# Hecquyn_SCH_Proto1_210523.net
KiCad netlist of a schematic drawn in Altium Designer
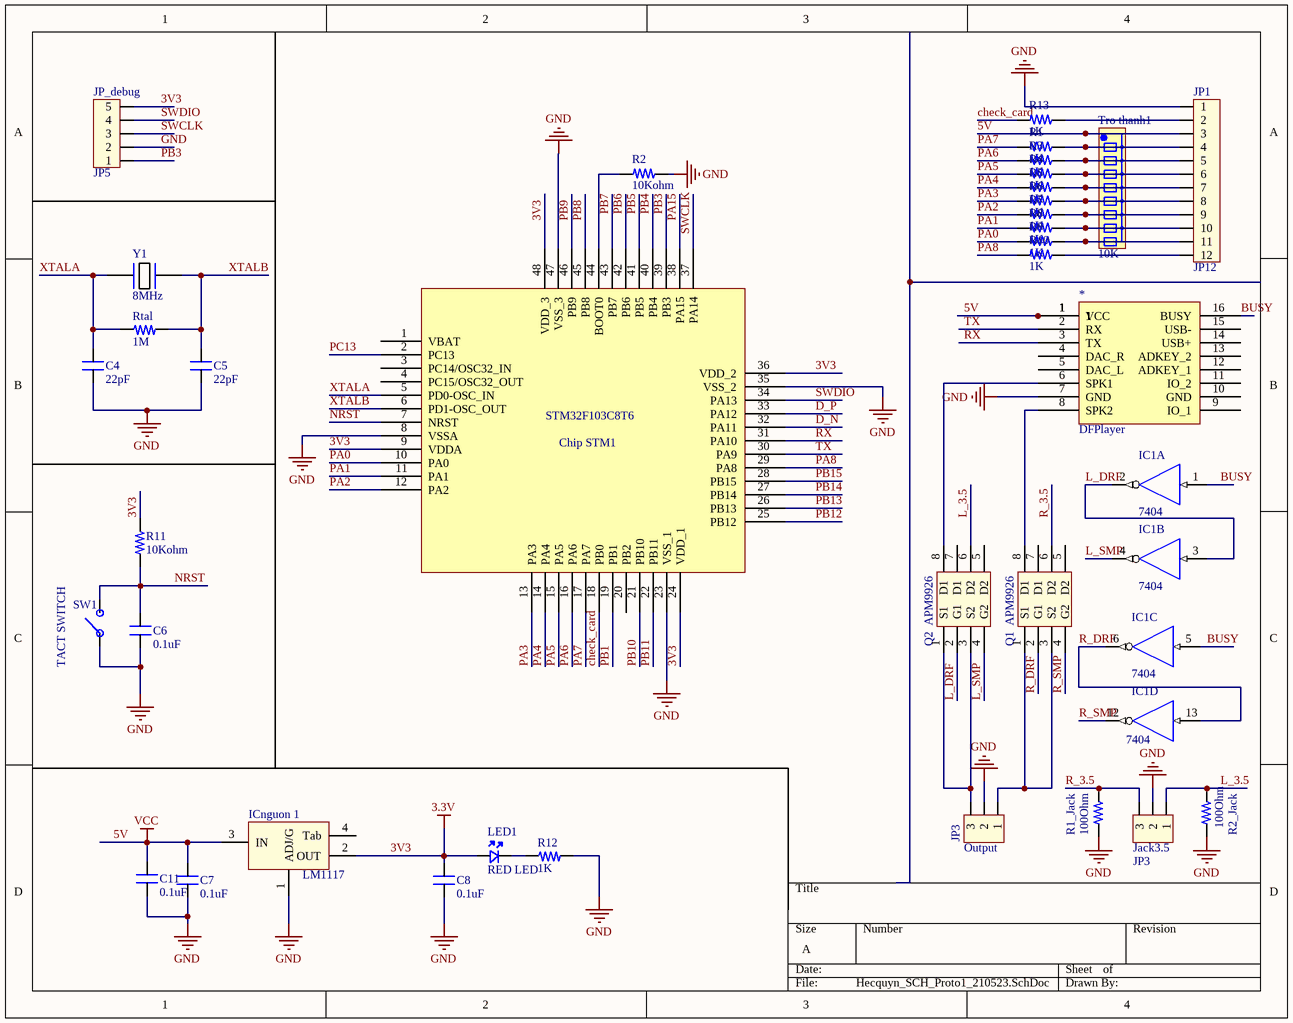
[diagram p0: Hecquyn_SCH_Proto1_210523.SchDoc]

(export (version "E")
  (design (tool "Eeschema 10.0.6"))
  (components
    (comp (ref "*")
      (value "DFPlayer")
      (footprint "DFplayer")
      (libsource (lib "Playersmd") (part "Component_1"))
    )
    (comp (ref "C4")
      (value "22pF")
      (footprint "CAP_0805")
      (description "22pF ±5% 50V Ceramic Capacitor C0G, NP0 0805 (2012 Metric)")
      (fields
        (field (name "MANUFACTURER") "KEMET")
        (field (name "MANUFACTURER PART NUMBER") "C0805C220J5GACTU")
      )
      (libsource (lib "STM_SCH_LIB") (part "CAP_22pF-50V-5%-0805"))
    )
    (comp (ref "C5")
      (value "22pF")
      (footprint "CAP_0805")
      (description "22pF ±5% 50V Ceramic Capacitor C0G, NP0 0805 (2012 Metric)")
      (fields
        (field (name "MANUFACTURER") "KEMET")
        (field (name "MANUFACTURER PART NUMBER") "C0805C220J5GACTU")
      )
      (libsource (lib "STM_SCH_LIB") (part "CAP_22pF-50V-5%-0805"))
    )
    (comp (ref "C6")
      (value "0.1uF")
      (footprint "CAP_0805")
      (description "0.1µF ±5% 50V Ceramic Capacitor X7R 0805 (2012 Metric)")
      (fields
        (field (name "MANUFACTURER") "KEMET")
        (field (name "MANUFACTURING PART NUMBER") "C0805C104J5RACTU")
      )
      (libsource (lib "STM_SCH_LIB") (part "CAP_0.1uF-50V-5%-0805"))
    )
    (comp (ref "C7")
      (value "0.1uF")
      (footprint "CAP_0805")
      (description "0.1µF ±5% 50V Ceramic Capacitor X7R 0805 (2012 Metric)")
      (fields
        (field (name "MANUFACTURER") "KEMET")
        (field (name "MANUFACTURING PART NUMBER") "C0805C104J5RACTU")
      )
      (libsource (lib "STM_SCH_LIB") (part "CAP_0.1uF-50V-5%-0805"))
    )
    (comp (ref "C8")
      (value "0.1uF")
      (footprint "CAP_0805")
      (description "0.1µF ±5% 50V Ceramic Capacitor X7R 0805 (2012 Metric)")
      (fields
        (field (name "MANUFACTURER") "KEMET")
        (field (name "MANUFACTURING PART NUMBER") "C0805C104J5RACTU")
      )
      (libsource (lib "STM_SCH_LIB") (part "CAP_0.1uF-50V-5%-0805"))
    )
    (comp (ref "C11")
      (value "0.1uF")
      (footprint "CAP_0805")
      (description "0.1µF ±5% 50V Ceramic Capacitor X7R 0805 (2012 Metric)")
      (fields
        (field (name "MANUFACTURER") "KEMET")
        (field (name "MANUFACTURING PART NUMBER") "C0805C104J5RACTU")
      )
      (libsource (lib "STM_SCH_LIB") (part "CAP_0.1uF-50V-5%-0805"))
    )
    (comp (ref "Chip STM1")
      (value "STM32F103C8T6")
      (footprint "LQFP-48_19.6_393_58X11_SMD")
      (description "ARM® Cortex®-M3 STM32F1 Microcontroller IC 32-Bit 72MHz 64KB (64K x 8) FLASH")
      (fields (field (name "MANUFACTURER") "STMicroelectronics"))
      (libsource (lib "STM_SCH_LIB") (part "IC-STM32F103C8T6 _1"))
    )
    (comp (ref "IC1")
      (value "7404")
      (footprint "DIP14/W0.3")
      (description "Hex Inverter")
      (libsource (lib "syhaunguyen") (part "7404"))
    )
    (comp (ref "ICnguon 1")
      (value "LM1117")
      (footprint "SOT223-4N")
      (description "3v3")
      (libsource (lib "syhaunguyen") (part "LM1117"))
    )
    (comp (ref "Jack3.5")
      (value "JP3")
      (footprint "CON3")
      (description "Connector 3")
      (libsource (lib "syhaunguyen") (part "Con3"))
    )
    (comp (ref "JP1")
      (value "JP12")
      (footprint "CON12")
      (description "Connector 12")
      (libsource (lib "syhaunguyen") (part "Con12"))
    )
    (comp (ref "JP_debug")
      (value "JP5")
      (footprint "CON5")
      (description "Connector 5")
      (libsource (lib "syhaunguyen") (part "Con5"))
    )
    (comp (ref "LED1")
      (value "RED LED")
      (footprint "LED_0805")
      (description "Red 621nm LED Indication - Discrete 2V 0805 (2012 Metric)")
      (fields
        (field (name "MANUFACTURER") "Lite-On Inc.")
        (field (name "MANUFACTURER PART NUMBER") "LTST-C170EKT")
      )
      (libsource (lib "STM_SCH_LIB") (part "LED-RED_10mA-0805"))
    )
    (comp (ref "Output")
      (value "JP3")
      (footprint "CON3")
      (description "Connector 3")
      (libsource (lib "syhaunguyen") (part "Con3"))
    )
    (comp (ref "Q1")
      (value "APM9926")
      (footprint "SO-8")
      (description "Dual P-Channel Enhancement Mode MOSFET")
      (libsource (lib "syhaunguyen") (part "APM4953"))
    )
    (comp (ref "Q2")
      (value "APM9926")
      (footprint "SO-8")
      (description "Dual P-Channel Enhancement Mode MOSFET")
      (libsource (lib "syhaunguyen") (part "APM4953"))
    )
    (comp (ref "R1")
      (value "1K")
      (footprint "RES_0805")
      (description "1 kOhms ±1% 0.125W, 1/8W Chip Resistor 0805 (2012 Metric) Moisture Resistant Thick Film")
      (fields (field (name "MANUFACTURER") "垈㎵á") (field (name "MANUFACTURER PART NUMBER") "RC0805FR-071KL"))
      (libsource (lib "STM_SCH_LIB") (part "RES_1K-0.125W-1%-0805"))
    )
    (comp (ref "R1_Jack")
      (value "100Ohm")
      (footprint "RES_0805")
      (description "1 kOhms ±1% 0.125W, 1/8W Chip Resistor 0805 (2012 Metric) Moisture Resistant Thick Film")
      (fields (field (name "MANUFACTURER") "垈㎵á") (field (name "MANUFACTURER PART NUMBER") "RC0805FR-071KL"))
      (libsource (lib "STM_SCH_LIB") (part "RES_1K-0.125W-1%-0805"))
    )
    (comp (ref "R2")
      (value "10Kohm")
      (footprint "RES_0805")
      (description "10 kOhms ±1% 0.125W, 1/8W Chip Resistor 0805 (2012 Metric) Moisture Resistant Thick Film")
      (fields
        (field (name "MANUFACTURER") "Yageo")
        (field (name "MANUFACTURING PART NUMBER") "RC0805FR-0710KL")
      )
      (libsource (lib "STM_SCH_LIB") (part "RES_10K-0.125W-1%-0805"))
    )
    (comp (ref "R2_Jack")
      (value "100Ohm")
      (footprint "RES_0805")
      (description "1 kOhms ±1% 0.125W, 1/8W Chip Resistor 0805 (2012 Metric) Moisture Resistant Thick Film")
      (fields (field (name "MANUFACTURER") "垈㎵á") (field (name "MANUFACTURER PART NUMBER") "RC0805FR-071KL"))
      (libsource (lib "STM_SCH_LIB") (part "RES_1K-0.125W-1%-0805"))
    )
    (comp (ref "R3")
      (value "1K")
      (footprint "RES_0805")
      (description "1 kOhms ±1% 0.125W, 1/8W Chip Resistor 0805 (2012 Metric) Moisture Resistant Thick Film")
      (fields (field (name "MANUFACTURER") "垈㎵á") (field (name "MANUFACTURER PART NUMBER") "RC0805FR-071KL"))
      (libsource (lib "STM_SCH_LIB") (part "RES_1K-0.125W-1%-0805"))
    )
    (comp (ref "R4")
      (value "1K")
      (footprint "RES_0805")
      (description "1 kOhms ±1% 0.125W, 1/8W Chip Resistor 0805 (2012 Metric) Moisture Resistant Thick Film")
      (fields (field (name "MANUFACTURER") "垈㎵á") (field (name "MANUFACTURER PART NUMBER") "RC0805FR-071KL"))
      (libsource (lib "STM_SCH_LIB") (part "RES_1K-0.125W-1%-0805"))
    )
    (comp (ref "R5")
      (value "1K")
      (footprint "RES_0805")
      (description "1 kOhms ±1% 0.125W, 1/8W Chip Resistor 0805 (2012 Metric) Moisture Resistant Thick Film")
      (fields (field (name "MANUFACTURER") "垈㎵á") (field (name "MANUFACTURER PART NUMBER") "RC0805FR-071KL"))
      (libsource (lib "STM_SCH_LIB") (part "RES_1K-0.125W-1%-0805"))
    )
    (comp (ref "R6")
      (value "1K")
      (footprint "RES_0805")
      (description "1 kOhms ±1% 0.125W, 1/8W Chip Resistor 0805 (2012 Metric) Moisture Resistant Thick Film")
      (fields (field (name "MANUFACTURER") "垈㎵á") (field (name "MANUFACTURER PART NUMBER") "RC0805FR-071KL"))
      (libsource (lib "STM_SCH_LIB") (part "RES_1K-0.125W-1%-0805"))
    )
    (comp (ref "R7")
      (value "1K")
      (footprint "RES_0805")
      (description "1 kOhms ±1% 0.125W, 1/8W Chip Resistor 0805 (2012 Metric) Moisture Resistant Thick Film")
      (fields (field (name "MANUFACTURER") "垈㎵á") (field (name "MANUFACTURER PART NUMBER") "RC0805FR-071KL"))
      (libsource (lib "STM_SCH_LIB") (part "RES_1K-0.125W-1%-0805"))
    )
    (comp (ref "R8")
      (value "1K")
      (footprint "RES_0805")
      (description "1 kOhms ±1% 0.125W, 1/8W Chip Resistor 0805 (2012 Metric) Moisture Resistant Thick Film")
      (fields (field (name "MANUFACTURER") "垈㎵á") (field (name "MANUFACTURER PART NUMBER") "RC0805FR-071KL"))
      (libsource (lib "STM_SCH_LIB") (part "RES_1K-0.125W-1%-0805"))
    )
    (comp (ref "R9")
      (value "1K")
      (footprint "RES_0805")
      (description "1 kOhms ±1% 0.125W, 1/8W Chip Resistor 0805 (2012 Metric) Moisture Resistant Thick Film")
      (fields (field (name "MANUFACTURER") "垈㎵á") (field (name "MANUFACTURER PART NUMBER") "RC0805FR-071KL"))
      (libsource (lib "STM_SCH_LIB") (part "RES_1K-0.125W-1%-0805"))
    )
    (comp (ref "R10")
      (value "1K")
      (footprint "RES_0805")
      (description "1 kOhms ±1% 0.125W, 1/8W Chip Resistor 0805 (2012 Metric) Moisture Resistant Thick Film")
      (fields (field (name "MANUFACTURER") "垈㎵á") (field (name "MANUFACTURER PART NUMBER") "RC0805FR-071KL"))
      (libsource (lib "STM_SCH_LIB") (part "RES_1K-0.125W-1%-0805"))
    )
    (comp (ref "R11")
      (value "10Kohm")
      (footprint "RES_0805")
      (fields
        (field (name "MANUFACTURER") "Rohm Semiconductor")
        (field (name "MANUFACTURING PART NUMBER") "KTR10EZPF1005")
      )
      (libsource (lib "STM_SCH_LIB") (part "RES_10MOHM-0.125W-1%-0805"))
    )
    (comp (ref "R12")
      (value "1K")
      (footprint "RES_0805")
      (description "1 kOhms ±1% 0.125W, 1/8W Chip Resistor 0805 (2012 Metric) Moisture Resistant Thick Film")
      (fields (field (name "MANUFACTURER") "垈㎵á") (field (name "MANUFACTURER PART NUMBER") "RC0805FR-071KL"))
      (libsource (lib "STM_SCH_LIB") (part "RES_1K-0.125W-1%-0805"))
    )
    (comp (ref "R13")
      (value "1K")
      (footprint "RES_0805")
      (description "1 kOhms ±1% 0.125W, 1/8W Chip Resistor 0805 (2012 Metric) Moisture Resistant Thick Film")
      (fields (field (name "MANUFACTURER") "垈㎵á") (field (name "MANUFACTURER PART NUMBER") "RC0805FR-071KL"))
      (libsource (lib "STM_SCH_LIB") (part "RES_1K-0.125W-1%-0805"))
    )
    (comp (ref "Rtal")
      (value "1M")
      (footprint "RES_0805")
      (fields
        (field (name "MANUFACTURER") "Rohm Semiconductor")
        (field (name "MANUFACTURING PART NUMBER") "KTR10EZPF1005")
      )
      (libsource (lib "STM_SCH_LIB") (part "RES_10MOHM-0.125W-1%-0805"))
    )
    (comp (ref "SW1")
      (value "TACT SWITCH")
      (footprint "SW_342_SMD")
      (description "Tactile Switch SPST-NO Top Actuated Surface Mount")
      (fields (field (name "MANUFACTURER") "C&K") (field (name "MANUFACTURING PART NUMBER") "KSR223GLFG"))
      (libsource (lib "STM_SCH_LIB") (part "SW_KSR223GLFG-SMD"))
    )
    (comp (ref "Tro thanh1")
      (value "10K")
      (footprint "RN8")
      (description "Resistor 8 (Thanh)")
      (libsource (lib "syhaunguyen") (part "RN8"))
    )
    (comp (ref "Y1")
      (value "8MHz")
      (footprint "XTAL_314_240X47_SMD")
      (description "Crystals 8MHz 22pF -20C 70C")
      (fields
        (field (name "MANUFACTURER") "IQD Frequency Products")
        (field (name "MANUFACTURING PART NUMBER") "LFXTAL030234Reel")
      )
      (libsource (lib "STM_SCH_LIB") (part "XTAL_8MHZ-LFXTAL030234"))
    )
  )
  (nets
    (net (code "1") (name "/BUSY") (class "Default")
      (node (ref "*") (pin "16") (pinfunction "BUSY_16") (pintype "passive"))
      (node (ref "IC1") (pin "1") (pinfunction "A_1") (pintype "input"))
      (node (ref "IC1") (pin "5") (pinfunction "A_5") (pintype "input"))
    )
    (net (code "2") (name "/D_N") (class "Default")
      (node (ref "Chip STM1") (pin "32") (pinfunction "PA11_32") (pintype "passive"))
    )
    (net (code "3") (name "/D_P") (class "Default")
      (node (ref "Chip STM1") (pin "33") (pinfunction "PA12_33") (pintype "passive"))
    )
    (net (code "4") (name "/L_3.5") (class "Default")
      (node (ref "Jack3.5") (pin "1") (pinfunction "1_1") (pintype "passive"))
      (node (ref "Q2") (pin "6") (pinfunction "D2_6") (pintype "passive"))
      (node (ref "R2_Jack") (pin "2") (pinfunction "2_2") (pintype "passive"))
    )
    (net (code "5") (name "/L_DRF") (class "Default")
      (node (ref "IC1") (pin "2") (pinfunction "~{O}_2") (pintype "output"))
      (node (ref "IC1") (pin "3") (pinfunction "A_3") (pintype "input"))
      (node (ref "Q2") (pin "2") (pinfunction "G1_2") (pintype "passive"))
    )
    (net (code "6") (name "/L_SMP") (class "Default")
      (node (ref "IC1") (pin "4") (pinfunction "~{O}_4") (pintype "output"))
      (node (ref "Q2") (pin "4") (pinfunction "G2_4") (pintype "passive"))
    )
    (net (code "7") (name "/NRST") (class "Default")
      (node (ref "C6") (pin "2") (pinfunction "2_2") (pintype "passive"))
      (node (ref "Chip STM1") (pin "7") (pinfunction "NRST_7") (pintype "passive"))
      (node (ref "R11") (pin "1") (pinfunction "1_1") (pintype "passive"))
      (node (ref "SW1") (pin "2") (pinfunction "2_2") (pintype "passive"))
    )
    (net (code "8") (name "/PA0") (class "Default")
      (node (ref "Chip STM1") (pin "10") (pinfunction "PA0_10") (pintype "passive"))
      (node (ref "R9") (pin "1") (pinfunction "1_1") (pintype "passive"))
    )
    (net (code "9") (name "/PA1") (class "Default")
      (node (ref "Chip STM1") (pin "11") (pinfunction "PA1_11") (pintype "passive"))
      (node (ref "R8") (pin "1") (pinfunction "1_1") (pintype "passive"))
    )
    (net (code "10") (name "/PA2") (class "Default")
      (node (ref "Chip STM1") (pin "12") (pinfunction "PA2_12") (pintype "passive"))
      (node (ref "R7") (pin "1") (pinfunction "1_1") (pintype "passive"))
    )
    (net (code "11") (name "/PA3") (class "Default")
      (node (ref "Chip STM1") (pin "13") (pinfunction "PA3_13") (pintype "passive"))
      (node (ref "R6") (pin "1") (pinfunction "1_1") (pintype "passive"))
    )
    (net (code "12") (name "/PA4") (class "Default")
      (node (ref "Chip STM1") (pin "14") (pinfunction "PA4_14") (pintype "passive"))
      (node (ref "R5") (pin "1") (pinfunction "1_1") (pintype "passive"))
    )
    (net (code "13") (name "/PA5") (class "Default")
      (node (ref "Chip STM1") (pin "15") (pinfunction "PA5_15") (pintype "passive"))
      (node (ref "R4") (pin "1") (pinfunction "1_1") (pintype "passive"))
    )
    (net (code "14") (name "/PA6") (class "Default")
      (node (ref "Chip STM1") (pin "16") (pinfunction "PA6_16") (pintype "passive"))
      (node (ref "R3") (pin "1") (pinfunction "1_1") (pintype "passive"))
    )
    (net (code "15") (name "/PA7") (class "Default")
      (node (ref "Chip STM1") (pin "17") (pinfunction "PA7_17") (pintype "passive"))
      (node (ref "R1") (pin "1") (pinfunction "1_1") (pintype "passive"))
    )
    (net (code "16") (name "/PA8") (class "Default")
      (node (ref "Chip STM1") (pin "29") (pinfunction "PA8_29") (pintype "passive"))
      (node (ref "R10") (pin "1") (pinfunction "1_1") (pintype "passive"))
    )
    (net (code "17") (name "/PA15") (class "Default")
      (node (ref "Chip STM1") (pin "38") (pinfunction "PA15_38") (pintype "passive"))
    )
    (net (code "18") (name "/PB1") (class "Default")
      (node (ref "Chip STM1") (pin "19") (pinfunction "PB1_19") (pintype "passive"))
    )
    (net (code "19") (name "/PB3") (class "Default")
      (node (ref "Chip STM1") (pin "39") (pinfunction "PB3_39") (pintype "passive"))
      (node (ref "JP_debug") (pin "1") (pinfunction "1_1") (pintype "passive"))
    )
    (net (code "20") (name "/PB4") (class "Default")
      (node (ref "Chip STM1") (pin "40") (pinfunction "PB4_40") (pintype "passive"))
    )
    (net (code "21") (name "/PB5") (class "Default")
      (node (ref "Chip STM1") (pin "41") (pinfunction "PB5_41") (pintype "passive"))
    )
    (net (code "22") (name "/PB6") (class "Default")
      (node (ref "Chip STM1") (pin "42") (pinfunction "PB6_42") (pintype "passive"))
    )
    (net (code "23") (name "/PB7") (class "Default")
      (node (ref "Chip STM1") (pin "43") (pinfunction "PB7_43") (pintype "passive"))
    )
    (net (code "24") (name "/PB8") (class "Default")
      (node (ref "Chip STM1") (pin "45") (pinfunction "PB8_45") (pintype "passive"))
    )
    (net (code "25") (name "/PB9") (class "Default")
      (node (ref "Chip STM1") (pin "46") (pinfunction "PB9_46") (pintype "passive"))
    )
    (net (code "26") (name "/PB10") (class "Default")
      (node (ref "Chip STM1") (pin "21") (pinfunction "PB10_21") (pintype "passive"))
    )
    (net (code "27") (name "/PB11") (class "Default")
      (node (ref "Chip STM1") (pin "22") (pinfunction "PB11_22") (pintype "passive"))
    )
    (net (code "28") (name "/PB12") (class "Default")
      (node (ref "Chip STM1") (pin "25") (pinfunction "PB12_25") (pintype "passive"))
    )
    (net (code "29") (name "/PB13") (class "Default")
      (node (ref "Chip STM1") (pin "26") (pinfunction "PB13_26") (pintype "passive"))
    )
    (net (code "30") (name "/PB14") (class "Default")
      (node (ref "Chip STM1") (pin "27") (pinfunction "PB14_27") (pintype "passive"))
    )
    (net (code "31") (name "/PB15") (class "Default")
      (node (ref "Chip STM1") (pin "28") (pinfunction "PB15_28") (pintype "passive"))
    )
    (net (code "32") (name "/PC13") (class "Default")
      (node (ref "Chip STM1") (pin "2") (pinfunction "PC13_2") (pintype "passive"))
    )
    (net (code "33") (name "/RX") (class "Default")
      (node (ref "*") (pin "3") (pinfunction "TX_3") (pintype "passive"))
      (node (ref "Chip STM1") (pin "31") (pinfunction "PA10_31") (pintype "passive"))
    )
    (net (code "34") (name "/R_3.5") (class "Default")
      (node (ref "Jack3.5") (pin "3") (pinfunction "3_3") (pintype "passive"))
      (node (ref "Q1") (pin "6") (pinfunction "D2_6") (pintype "passive"))
      (node (ref "R1_Jack") (pin "2") (pinfunction "2_2") (pintype "passive"))
    )
    (net (code "35") (name "/R_DRF") (class "Default")
      (node (ref "IC1") (pin "13") (pinfunction "A_13") (pintype "input"))
      (node (ref "IC1") (pin "6") (pinfunction "~{O}_6") (pintype "output"))
      (node (ref "Q1") (pin "2") (pinfunction "G1_2") (pintype "passive"))
    )
    (net (code "36") (name "/R_SMP") (class "Default")
      (node (ref "IC1") (pin "12") (pinfunction "~{O}_12") (pintype "output"))
      (node (ref "Q1") (pin "4") (pinfunction "G2_4") (pintype "passive"))
    )
    (net (code "37") (name "/SWCLK") (class "Default")
      (node (ref "Chip STM1") (pin "37") (pinfunction "PA14_37") (pintype "passive"))
      (node (ref "JP_debug") (pin "3") (pinfunction "3_3") (pintype "passive"))
    )
    (net (code "38") (name "/SWDIO") (class "Default")
      (node (ref "Chip STM1") (pin "34") (pinfunction "PA13_34") (pintype "passive"))
      (node (ref "JP_debug") (pin "4") (pinfunction "4_4") (pintype "passive"))
    )
    (net (code "39") (name "/TX") (class "Default")
      (node (ref "*") (pin "2") (pinfunction "RX_2") (pintype "passive"))
      (node (ref "Chip STM1") (pin "30") (pinfunction "PA9_30") (pintype "passive"))
    )
    (net (code "40") (name "/XTALA") (class "Default")
      (node (ref "C4") (pin "2") (pinfunction "2_2") (pintype "passive"))
      (node (ref "Chip STM1") (pin "5") (pinfunction "PD0-OSC_IN_5") (pintype "passive"))
      (node (ref "Rtal") (pin "2") (pinfunction "2_2") (pintype "passive"))
      (node (ref "Y1") (pin "1") (pinfunction "1_1") (pintype "passive"))
    )
    (net (code "41") (name "/XTALB") (class "Default")
      (node (ref "C5") (pin "2") (pinfunction "2_2") (pintype "passive"))
      (node (ref "Chip STM1") (pin "6") (pinfunction "PD1-OSC_OUT_6") (pintype "passive"))
      (node (ref "Rtal") (pin "1") (pinfunction "1_1") (pintype "passive"))
      (node (ref "Y1") (pin "2") (pinfunction "2_2") (pintype "passive"))
    )
    (net (code "42") (name "/check_card") (class "Default")
      (node (ref "Chip STM1") (pin "18") (pinfunction "PB0_18") (pintype "passive"))
      (node (ref "R13") (pin "1") (pinfunction "1_1") (pintype "passive"))
    )
    (net (code "43") (name "3.3V") (class "Default")
      (node (ref "C8") (pin "2") (pinfunction "2_2") (pintype "passive"))
      (node (ref "Chip STM1") (pin "24") (pinfunction "VDD_1_24") (pintype "passive"))
      (node (ref "Chip STM1") (pin "36") (pinfunction "VDD_2_36") (pintype "passive"))
      (node (ref "Chip STM1") (pin "48") (pinfunction "VDD_3_48") (pintype "passive"))
      (node (ref "Chip STM1") (pin "9") (pinfunction "VDDA_9") (pintype "passive"))
      (node (ref "ICnguon 1") (pin "2") (pinfunction "OUT_2") (pintype "passive"))
      (node (ref "JP_debug") (pin "5") (pinfunction "5_5") (pintype "passive"))
      (node (ref "LED1") (pin "A") (pinfunction "A_A") (pintype "passive"))
      (node (ref "R11") (pin "2") (pinfunction "2_2") (pintype "passive"))
    )
    (net (code "44") (name "GND") (class "Default")
      (node (ref "*") (pin "7") (pinfunction "GND_7") (pintype "passive"))
      (node (ref "C11") (pin "1") (pinfunction "1_1") (pintype "passive"))
      (node (ref "C4") (pin "1") (pinfunction "1_1") (pintype "passive"))
      (node (ref "C5") (pin "1") (pinfunction "1_1") (pintype "passive"))
      (node (ref "C6") (pin "1") (pinfunction "1_1") (pintype "passive"))
      (node (ref "C7") (pin "1") (pinfunction "1_1") (pintype "passive"))
      (node (ref "C8") (pin "1") (pinfunction "1_1") (pintype "passive"))
      (node (ref "Chip STM1") (pin "23") (pinfunction "VSS_1_23") (pintype "passive"))
      (node (ref "Chip STM1") (pin "35") (pinfunction "VSS_2_35") (pintype "passive"))
      (node (ref "Chip STM1") (pin "47") (pinfunction "VSS_3_47") (pintype "passive"))
      (node (ref "Chip STM1") (pin "8") (pinfunction "VSSA_8") (pintype "passive"))
      (node (ref "IC1") (pin "7") (pinfunction "GND_7") (pintype "power_in"))
      (node (ref "ICnguon 1") (pin "1") (pinfunction "ADJ/G_1") (pintype "passive"))
      (node (ref "JP1") (pin "1") (pinfunction "1_1") (pintype "passive"))
      (node (ref "JP_debug") (pin "2") (pinfunction "2_2") (pintype "passive"))
      (node (ref "Jack3.5") (pin "2") (pinfunction "2_2") (pintype "passive"))
      (node (ref "Output") (pin "2") (pinfunction "2_2") (pintype "passive"))
      (node (ref "R12") (pin "1") (pinfunction "1_1") (pintype "passive"))
      (node (ref "R1_Jack") (pin "1") (pinfunction "1_1") (pintype "passive"))
      (node (ref "R2") (pin "2") (pinfunction "2_2") (pintype "passive"))
      (node (ref "R2_Jack") (pin "1") (pinfunction "1_1") (pintype "passive"))
      (node (ref "SW1") (pin "1") (pinfunction "1_1") (pintype "passive"))
    )
    (net (code "45") (name "Net-(*-SPK1)") (class "Default")
      (node (ref "*") (pin "6") (pinfunction "SPK1_6") (pintype "passive"))
      (node (ref "Q2") (pin "8") (pinfunction "D1_8") (pintype "passive"))
    )
    (net (code "46") (name "Net-(*-SPK2)") (class "Default")
      (node (ref "*") (pin "8") (pinfunction "SPK2_8") (pintype "passive"))
      (node (ref "Q1") (pin "8") (pinfunction "D1_8") (pintype "passive"))
    )
    (net (code "47") (name "Net-(Chip STM1-BOOT0)") (class "Default")
      (node (ref "Chip STM1") (pin "44") (pinfunction "BOOT0_44") (pintype "passive"))
      (node (ref "R2") (pin "1") (pinfunction "1_1") (pintype "passive"))
    )
    (net (code "48") (name "Net-(JP1-Pad2)") (class "Default")
      (node (ref "JP1") (pin "2") (pinfunction "2_2") (pintype "passive"))
      (node (ref "R13") (pin "2") (pinfunction "2_2") (pintype "passive"))
    )
    (net (code "49") (name "Net-(JP1-Pad4)") (class "Default")
      (node (ref "JP1") (pin "4") (pinfunction "4_4") (pintype "passive"))
      (node (ref "R1") (pin "2") (pinfunction "2_2") (pintype "passive"))
      (node (ref "Tro thanh1") (pin "2") (pinfunction "2_2") (pintype "passive"))
    )
    (net (code "50") (name "Net-(JP1-Pad5)") (class "Default")
      (node (ref "JP1") (pin "5") (pinfunction "5_5") (pintype "passive"))
      (node (ref "R3") (pin "2") (pinfunction "2_2") (pintype "passive"))
      (node (ref "Tro thanh1") (pin "3") (pinfunction "3_3") (pintype "passive"))
    )
    (net (code "51") (name "Net-(JP1-Pad6)") (class "Default")
      (node (ref "JP1") (pin "6") (pinfunction "6_6") (pintype "passive"))
      (node (ref "R4") (pin "2") (pinfunction "2_2") (pintype "passive"))
      (node (ref "Tro thanh1") (pin "4") (pinfunction "4_4") (pintype "passive"))
    )
    (net (code "52") (name "Net-(JP1-Pad7)") (class "Default")
      (node (ref "JP1") (pin "7") (pinfunction "7_7") (pintype "passive"))
      (node (ref "R5") (pin "2") (pinfunction "2_2") (pintype "passive"))
      (node (ref "Tro thanh1") (pin "5") (pinfunction "5_5") (pintype "passive"))
    )
    (net (code "53") (name "Net-(JP1-Pad8)") (class "Default")
      (node (ref "JP1") (pin "8") (pinfunction "8_8") (pintype "passive"))
      (node (ref "R6") (pin "2") (pinfunction "2_2") (pintype "passive"))
      (node (ref "Tro thanh1") (pin "6") (pinfunction "6_6") (pintype "passive"))
    )
    (net (code "54") (name "Net-(JP1-Pad9)") (class "Default")
      (node (ref "JP1") (pin "9") (pinfunction "9_9") (pintype "passive"))
      (node (ref "R7") (pin "2") (pinfunction "2_2") (pintype "passive"))
      (node (ref "Tro thanh1") (pin "7") (pinfunction "7_7") (pintype "passive"))
    )
    (net (code "55") (name "Net-(JP1-Pad10)") (class "Default")
      (node (ref "JP1") (pin "10") (pinfunction "10_10") (pintype "passive"))
      (node (ref "R8") (pin "2") (pinfunction "2_2") (pintype "passive"))
      (node (ref "Tro thanh1") (pin "8") (pinfunction "8_8") (pintype "passive"))
    )
    (net (code "56") (name "Net-(JP1-Pad11)") (class "Default")
      (node (ref "JP1") (pin "11") (pinfunction "11_11") (pintype "passive"))
      (node (ref "R9") (pin "2") (pinfunction "2_2") (pintype "passive"))
      (node (ref "Tro thanh1") (pin "9") (pinfunction "9_9") (pintype "passive"))
    )
    (net (code "57") (name "Net-(JP1-Pad12)") (class "Default")
      (node (ref "JP1") (pin "12") (pinfunction "12_12") (pintype "passive"))
      (node (ref "R10") (pin "2") (pinfunction "2_2") (pintype "passive"))
    )
    (net (code "58") (name "Net-(LED1-PadK)") (class "Default")
      (node (ref "LED1") (pin "K") (pinfunction "K_K") (pintype "passive"))
      (node (ref "R12") (pin "2") (pinfunction "2_2") (pintype "passive"))
    )
    (net (code "59") (name "Net-(Q1-S1)") (class "Default")
      (node (ref "Output") (pin "1") (pinfunction "1_1") (pintype "passive"))
      (node (ref "Q1") (pin "1") (pinfunction "S1_1") (pintype "passive"))
      (node (ref "Q1") (pin "3") (pinfunction "S2_3") (pintype "passive"))
    )
    (net (code "60") (name "Net-(Q2-S1)") (class "Default")
      (node (ref "Output") (pin "3") (pinfunction "3_3") (pintype "passive"))
      (node (ref "Q2") (pin "1") (pinfunction "S1_1") (pintype "passive"))
      (node (ref "Q2") (pin "3") (pinfunction "S2_3") (pintype "passive"))
    )
    (net (code "61") (name "VCC") (class "Default")
      (node (ref "*") (pin "1") (pinfunction "1_1") (pintype "passive"))
      (node (ref "C11") (pin "2") (pinfunction "2_2") (pintype "passive"))
      (node (ref "C7") (pin "2") (pinfunction "2_2") (pintype "passive"))
      (node (ref "IC1") (pin "14") (pinfunction "VCC_14") (pintype "power_in"))
      (node (ref "ICnguon 1") (pin "3") (pinfunction "IN_3") (pintype "passive"))
      (node (ref "JP1") (pin "3") (pinfunction "3_3") (pintype "passive"))
      (node (ref "Tro thanh1") (pin "1") (pinfunction "1_1") (pintype "passive"))
    )
    (net (code "62") (name "unconnected-(*-ADKEY_1-Pad12)") (class "Default")
      (node (ref "*") (pin "12") (pinfunction "ADKEY_1_12") (pintype "passive"))
    )
    (net (code "63") (name "unconnected-(*-ADKEY_2-Pad13)") (class "Default")
      (node (ref "*") (pin "13") (pinfunction "ADKEY_2_13") (pintype "passive"))
    )
    (net (code "64") (name "unconnected-(*-DAC_L-Pad5)") (class "Default")
      (node (ref "*") (pin "5") (pinfunction "DAC_L_5") (pintype "passive"))
    )
    (net (code "65") (name "unconnected-(*-DAC_R-Pad4)") (class "Default")
      (node (ref "*") (pin "4") (pinfunction "DAC_R_4") (pintype "passive"))
    )
    (net (code "66") (name "unconnected-(*-GND-Pad10)") (class "Default")
      (node (ref "*") (pin "10") (pinfunction "GND_10") (pintype "passive"))
    )
    (net (code "67") (name "unconnected-(*-IO_1-Pad9)") (class "Default")
      (node (ref "*") (pin "9") (pinfunction "IO_1_9") (pintype "passive"))
    )
    (net (code "68") (name "unconnected-(*-IO_2-Pad11)") (class "Default")
      (node (ref "*") (pin "11") (pinfunction "IO_2_11") (pintype "passive"))
    )
    (net (code "69") (name "unconnected-(*-USB+-Pad14)") (class "Default")
      (node (ref "*") (pin "14") (pinfunction "USB+_14") (pintype "passive"))
    )
    (net (code "70") (name "unconnected-(*-USB--Pad15)") (class "Default")
      (node (ref "*") (pin "15") (pinfunction "USB-_15") (pintype "passive"))
    )
    (net (code "71") (name "unconnected-(Chip STM1-PB2-Pad20)") (class "Default")
      (node (ref "Chip STM1") (pin "20") (pinfunction "PB2_20") (pintype "passive"))
    )
    (net (code "72") (name "unconnected-(Chip STM1-PC14{slash}OSC32_IN-Pad3)") (class "Default")
      (node (ref "Chip STM1") (pin "3") (pinfunction "PC14/OSC32_IN_3") (pintype "passive"))
    )
    (net (code "73") (name "unconnected-(Chip STM1-PC15{slash}OSC32_OUT-Pad4)") (class "Default")
      (node (ref "Chip STM1") (pin "4") (pinfunction "PC15/OSC32_OUT_4") (pintype "passive"))
    )
    (net (code "74") (name "unconnected-(Chip STM1-VBAT-Pad1)") (class "Default")
      (node (ref "Chip STM1") (pin "1") (pinfunction "VBAT_1") (pintype "passive"))
    )
    (net (code "75") (name "unconnected-(ICnguon 1-Tab-Pad4)") (class "Default")
      (node (ref "ICnguon 1") (pin "4") (pinfunction "Tab_4") (pintype "passive"))
    )
    (net (code "76") (name "unconnected-(Q1-D1-Pad7)") (class "Default")
      (node (ref "Q1") (pin "7") (pinfunction "D1_7") (pintype "passive"))
    )
    (net (code "77") (name "unconnected-(Q1-D2-Pad5)") (class "Default")
      (node (ref "Q1") (pin "5") (pinfunction "D2_5") (pintype "passive"))
    )
    (net (code "78") (name "unconnected-(Q2-D1-Pad7)") (class "Default")
      (node (ref "Q2") (pin "7") (pinfunction "D1_7") (pintype "passive"))
    )
    (net (code "79") (name "unconnected-(Q2-D2-Pad5)") (class "Default")
      (node (ref "Q2") (pin "5") (pinfunction "D2_5") (pintype "passive"))
    )
  )
)
